# PROC106B_BT_DISPLAY.net
KiCad netlist of a schematic drawn in Altium Designer
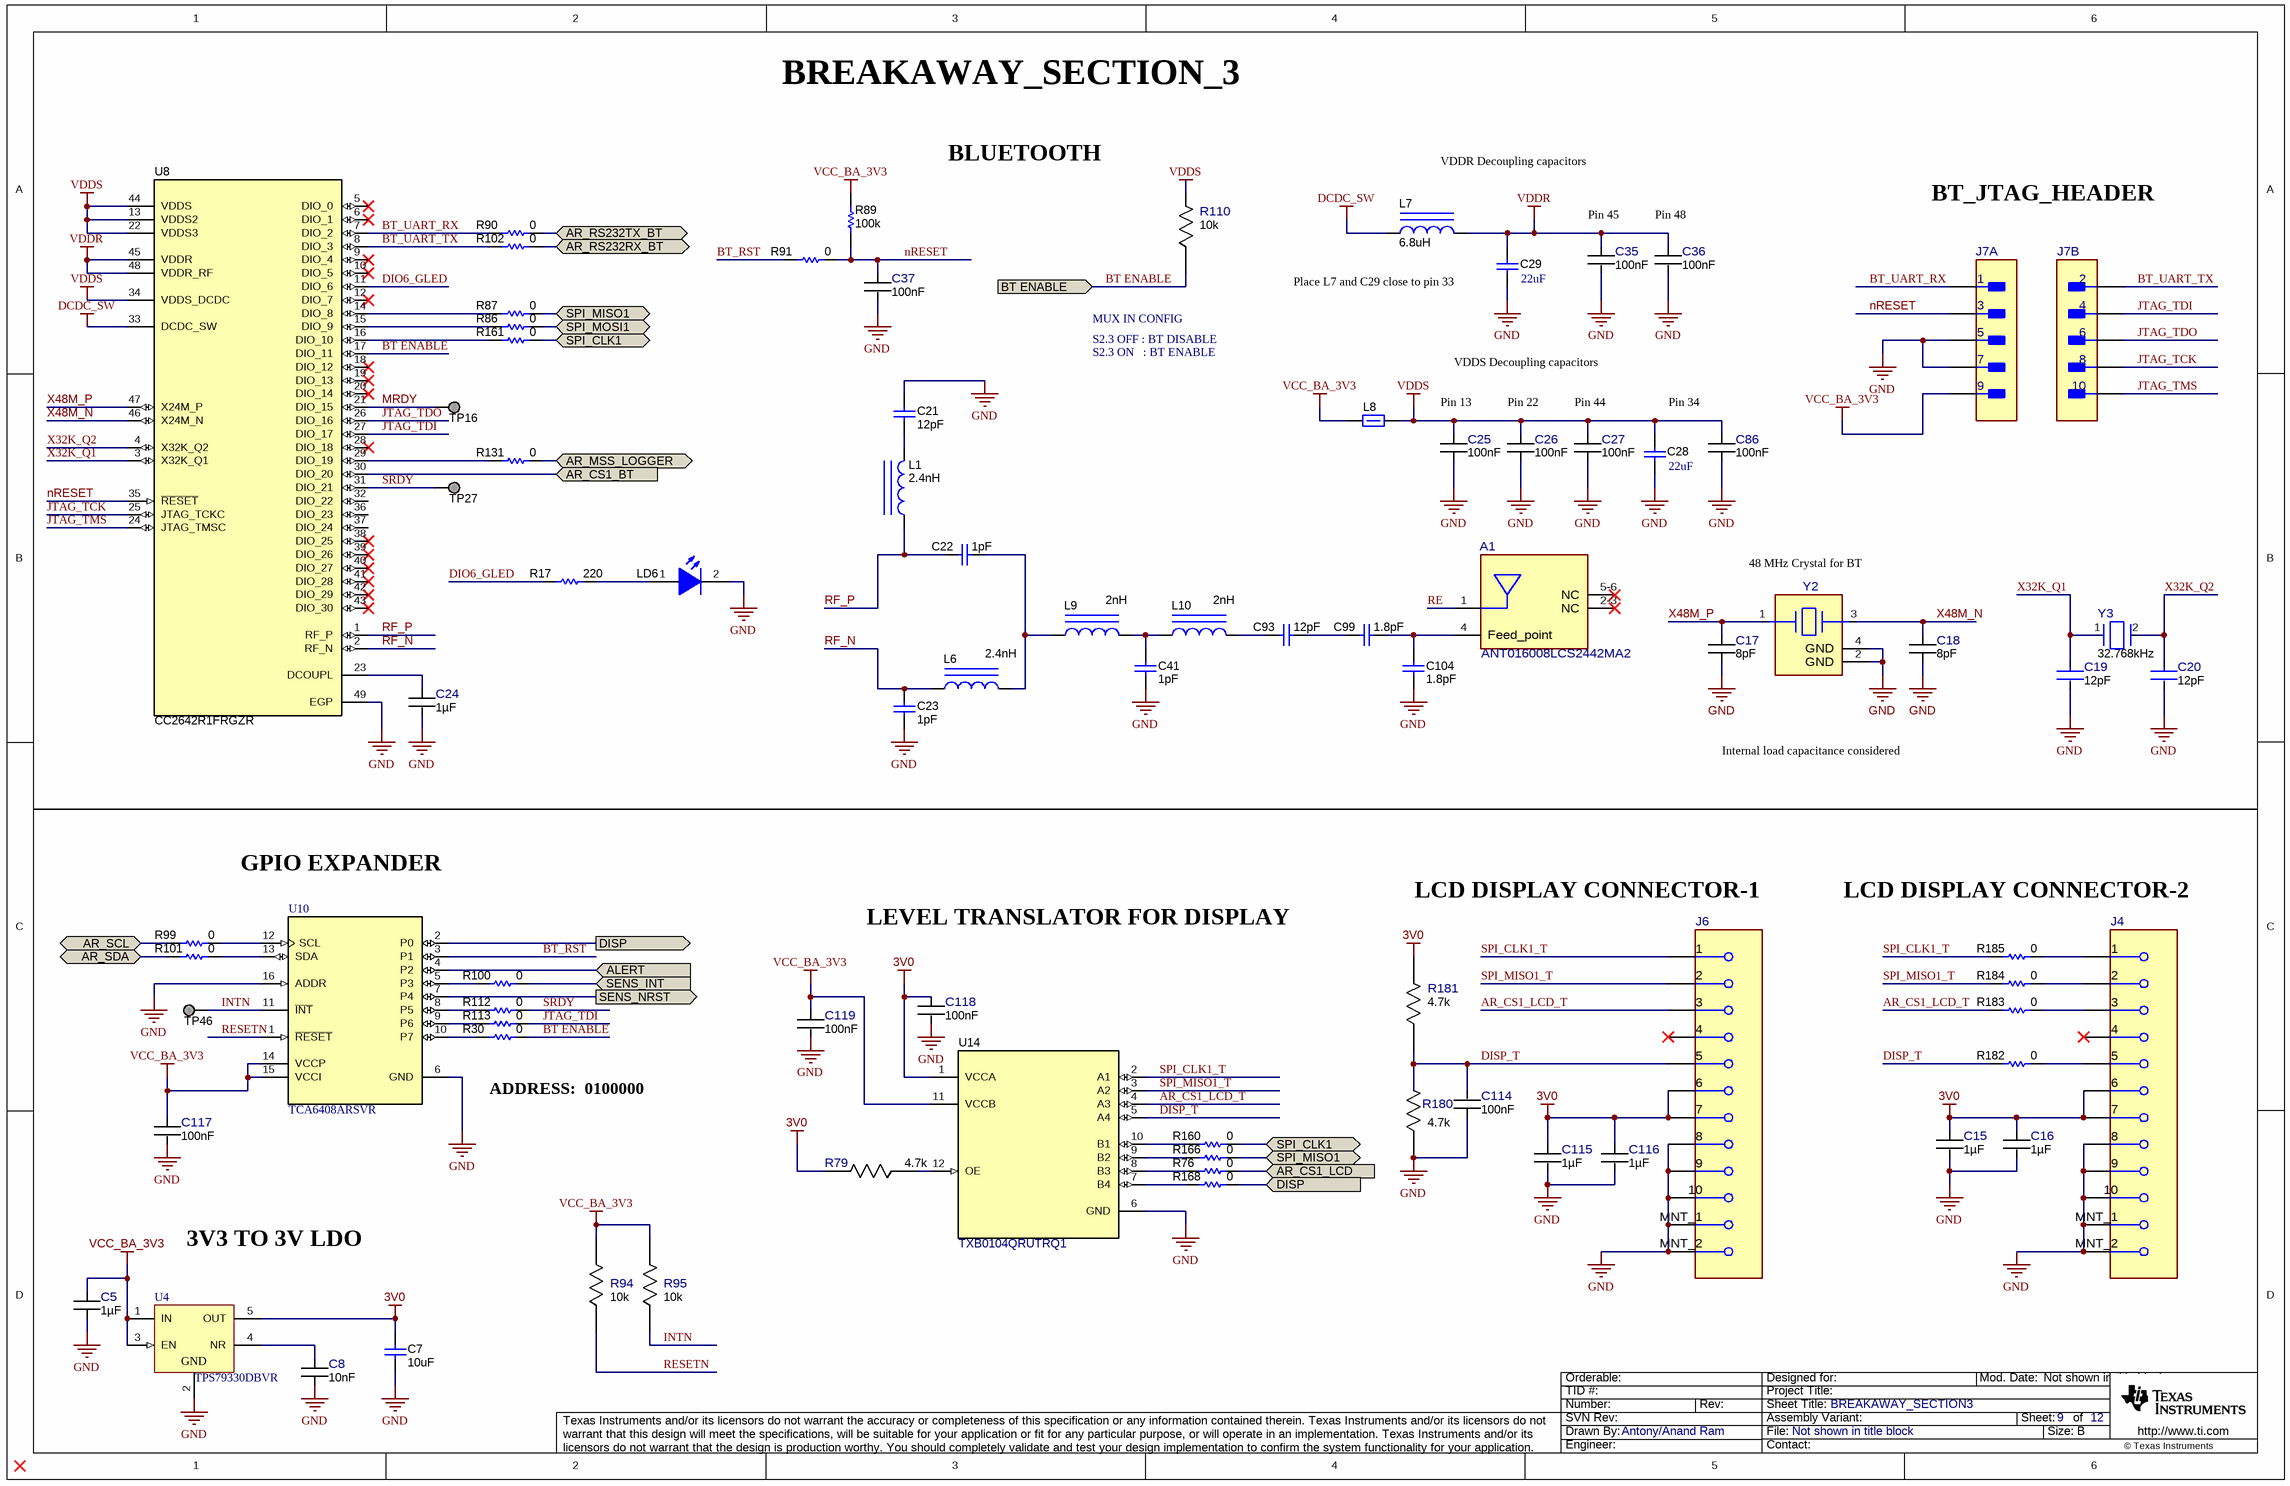
[diagram p0: PROC106B_BT_DISPLAY.SchDoc]

(export (version "E")
  (design (tool "Eeschema 10.0.6"))
  (components
    (comp (ref "A1")
      (value "ANT016008LCS2442MA2")
      (footprint "FP-ANT016008LCS2442MA2_SMT_ANT-0")
      (description "RF ANT 2.4GHZ CHIP SOLDER SMD")
      (fields (field (name "MANUFACTURER") "TDK Corporation"))
      (libsource (lib "Altium Vault - TI") (part "SYM-ANT016008LCS2442MA2"))
    )
    (comp (ref "C5")
      (value "CL03A105MO3NRNH")
      (footprint "FP-CL03A105MO3NRNH_0201-IPC_C")
      (description "1µF ±20% 16V Ceramic Capacitor X5R 0201")
      (fields (field (name "CAP_F") "1µF") (field (name "MANUFACTURER") "Samsung Electro-Mechanics"))
      (libsource (lib "Altium Vault - TI") (part "SYM-B32642B0223J"))
    )
    (comp (ref "C7")
      (value "10uF")
      (footprint "0402_070")
      (description "CAP, CERM, 10 uF, 10 V, +/- 20%, X5R, 0402")
      (fields
        (field (name "MANUFACTURER") "Samsung Electro-Mechanics")
        (field (name "PARTNUMBER") "CL05A106MP5NUNC")
      )
      (libsource (lib "Altium Vault - TI") (part "Capacitor"))
    )
    (comp (ref "C8")
      (value "CL03A103KA3NNNC")
      (footprint "FP-CL03A103KA3NNNC_0201-IPC_C")
      (description "CAP CER 10000PF 25V X5R 0201")
      (fields
        (field (name "CAP_F") "10nF")
        (field (name "MANUFACTURER") "Samsung Electro-Mechanics America, Inc")
      )
      (libsource (lib "Altium Vault - TI") (part "SYM-B32642B0223J"))
    )
    (comp (ref "C15")
      (value "CL03A105MO3NRNH")
      (footprint "FP-CL03A105MO3NRNH_0201-IPC_C")
      (description "1µF ±20% 16V Ceramic Capacitor X5R 0201")
      (fields (field (name "CAP_F") "1µF") (field (name "MANUFACTURER") "Samsung Electro-Mechanics"))
      (libsource (lib "Altium Vault - TI") (part "SYM-B32642B0223J"))
    )
    (comp (ref "C16")
      (value "CL03A105MO3NRNH")
      (footprint "FP-CL03A105MO3NRNH_0201-IPC_C")
      (description "1µF ±20% 16V Ceramic Capacitor X5R 0201")
      (fields (field (name "CAP_F") "1µF") (field (name "MANUFACTURER") "Samsung Electro-Mechanics"))
      (libsource (lib "Altium Vault - TI") (part "SYM-B32642B0223J"))
    )
    (comp (ref "C17")
      (value "GRM0335C1H8R0BA01D")
      (footprint "FP-GRM0335C1H8R0BA01D_0201 (0603 metric)-IPC_C")
      (description "Cap Ceramic 8pF 50V C0G 0.1pF SMD 0201 125°C Paper T/R")
      (fields (field (name "CAP_F") "8pF") (field (name "MANUFACTURER") "Murata"))
      (libsource (lib "Altium Vault - TI") (part "SYM-B32642B0223J"))
    )
    (comp (ref "C18")
      (value "GRM0335C1H8R0BA01D")
      (footprint "FP-GRM0335C1H8R0BA01D_0201 (0603 metric)-IPC_C")
      (description "Cap Ceramic 8pF 50V C0G 0.1pF SMD 0201 125°C Paper T/R")
      (fields (field (name "CAP_F") "8pF") (field (name "MANUFACTURER") "Murata"))
      (libsource (lib "Altium Vault - TI") (part "SYM-B32642B0223J"))
    )
    (comp (ref "C19")
      (value "250R05L120JV4T")
      (footprint "FP-250R05L120JV4T_0201-IPC_C")
      (description "CAP CER 12PF 25V C0G/NP0 0201")
      (fields (field (name "CAP_F") "12pF") (field (name "MANUFACTURER") "Johanson Technology Inc."))
      (libsource (lib "Altium Vault - TI") (part "SYM-CL31B335KAHVPNE"))
    )
    (comp (ref "C20")
      (value "250R05L120JV4T")
      (footprint "FP-250R05L120JV4T_0201-IPC_C")
      (description "CAP CER 12PF 25V C0G/NP0 0201")
      (fields (field (name "CAP_F") "12pF") (field (name "MANUFACTURER") "Johanson Technology Inc."))
      (libsource (lib "Altium Vault - TI") (part "SYM-CL31B335KAHVPNE"))
    )
    (comp (ref "C21")
      (value "CL05C120JB5NNNC")
      (footprint "0402L")
      (description "CAP, CERM, 12 pF, 50 V, +/- 5%, C0G/NP0, 0402")
      (fields
        (field (name "MANUFACTURER") "Samsung Electro-Mechanics")
        (field (name "VALUEDISPLAYED") "12pF")
        (field (name "PUBLISHER") "Texas Instruments")
      )
      (libsource (lib "Altium Vault - TI") (part "Capacitor"))
    )
    (comp (ref "C22")
      (value "GCM1555C1H1R0CA16D")
      (footprint "0402L")
      (description "CAP, CERM, 1 pF, 50 V,+/- 25%, C0G/NP0, AEC-Q200 Grade 1, 0402")
      (fields (field (name "VALUEDISPLAYED") "1pF") (field (name "MANUFACTURER") "MuRata"))
      (libsource (lib "Altium Vault - TI") (part "Capacitor"))
    )
    (comp (ref "C23")
      (value "GCM1555C1H1R0CA16D")
      (footprint "0402L")
      (description "CAP, CERM, 1 pF, 50 V,+/- 25%, C0G/NP0, AEC-Q200 Grade 1, 0402")
      (fields (field (name "VALUEDISPLAYED") "1pF") (field (name "MANUFACTURER") "MuRata"))
      (libsource (lib "Altium Vault - TI") (part "Capacitor"))
    )
    (comp (ref "C24")
      (value "CL03A105MO3NRNH")
      (footprint "FP-CL03A105MO3NRNH_0201-IPC_C")
      (description "1µF ±20% 16V Ceramic Capacitor X5R 0201")
      (fields (field (name "CAP_F") "1µF") (field (name "MANUFACTURER") "Samsung Electro-Mechanics"))
      (libsource (lib "Altium Vault - TI") (part "SYM-B32642B0223J"))
    )
    (comp (ref "C25")
      (value "GRM033R6YA104KE14D")
      (footprint "FP-GRM033R6YA104KE14D_0201 (0603 Metric)-IPC_C")
      (description "Cap Ceramic 0.1uF 35V X5R 10% Pad SMD 0201 85C T/R")
      (fields (field (name "CAP_F") "100nF") (field (name "MANUFACTURER") "Murata Electronics North America"))
      (libsource (lib "Altium Vault - TI") (part "SYM-B32642B0223J"))
    )
    (comp (ref "C26")
      (value "GRM033R6YA104KE14D")
      (footprint "FP-GRM033R6YA104KE14D_0201 (0603 Metric)-IPC_C")
      (description "Cap Ceramic 0.1uF 35V X5R 10% Pad SMD 0201 85C T/R")
      (fields (field (name "CAP_F") "100nF") (field (name "MANUFACTURER") "Murata Electronics North America"))
      (libsource (lib "Altium Vault - TI") (part "SYM-B32642B0223J"))
    )
    (comp (ref "C27")
      (value "GRM033R6YA104KE14D")
      (footprint "FP-GRM033R6YA104KE14D_0201 (0603 Metric)-IPC_C")
      (description "Cap Ceramic 0.1uF 35V X5R 10% Pad SMD 0201 85C T/R")
      (fields (field (name "CAP_F") "100nF") (field (name "MANUFACTURER") "Murata Electronics North America"))
      (libsource (lib "Altium Vault - TI") (part "SYM-B32642B0223J"))
    )
    (comp (ref "C28")
      (value "CL05A226MQ5N6J8")
      (footprint "0402S")
      (description "CAP CER 22UF 6.3V X5R 0402")
      (fields
        (field (name "MANUFACTURER") "Samsung Electro-Mechanics")
        (field (name "VALUEDISPLAYED") "22uF")
      )
      (libsource (lib "Altium Vault - TI") (part "Capacitor"))
    )
    (comp (ref "C29")
      (value "CL05A226MQ5N6J8")
      (footprint "0402S")
      (description "CAP CER 22UF 6.3V X5R 0402")
      (fields
        (field (name "MANUFACTURER") "Samsung Electro-Mechanics")
        (field (name "VALUEDISPLAYED") "22uF")
      )
      (libsource (lib "Altium Vault - TI") (part "Capacitor"))
    )
    (comp (ref "C35")
      (value "GRM033R6YA104KE14D")
      (footprint "FP-GRM033R6YA104KE14D_0201 (0603 Metric)-IPC_C")
      (description "Cap Ceramic 0.1uF 35V X5R 10% Pad SMD 0201 85C T/R")
      (fields (field (name "CAP_F") "100nF") (field (name "MANUFACTURER") "Murata Electronics North America"))
      (libsource (lib "Altium Vault - TI") (part "SYM-B32642B0223J"))
    )
    (comp (ref "C36")
      (value "GRM033R6YA104KE14D")
      (footprint "FP-GRM033R6YA104KE14D_0201 (0603 Metric)-IPC_C")
      (description "Cap Ceramic 0.1uF 35V X5R 10% Pad SMD 0201 85C T/R")
      (fields (field (name "CAP_F") "100nF") (field (name "MANUFACTURER") "Murata Electronics North America"))
      (libsource (lib "Altium Vault - TI") (part "SYM-B32642B0223J"))
    )
    (comp (ref "C37")
      (value "GRM033R6YA104KE14D")
      (footprint "FP-GRM033R6YA104KE14D_0201 (0603 Metric)-IPC_C")
      (description "Cap Ceramic 0.1uF 35V X5R 10% Pad SMD 0201 85C T/R")
      (fields (field (name "CAP_F") "100nF") (field (name "MANUFACTURER") "Murata Electronics North America"))
      (libsource (lib "Altium Vault - TI") (part "SYM-B32642B0223J"))
    )
    (comp (ref "C41")
      (value "GCM1555C1H1R0CA16D")
      (footprint "0402L")
      (description "CAP, CERM, 1 pF, 50 V,+/- 25%, C0G/NP0, AEC-Q200 Grade 1, 0402")
      (fields (field (name "VALUEDISPLAYED") "1pF") (field (name "MANUFACTURER") "MuRata"))
      (libsource (lib "Altium Vault - TI") (part "Capacitor"))
    )
    (comp (ref "C86")
      (value "GRM033R6YA104KE14D")
      (footprint "FP-GRM033R6YA104KE14D_0201 (0603 Metric)-IPC_C")
      (description "Cap Ceramic 0.1uF 35V X5R 10% Pad SMD 0201 85C T/R")
      (fields (field (name "CAP_F") "100nF") (field (name "MANUFACTURER") "Murata Electronics North America"))
      (libsource (lib "Altium Vault - TI") (part "SYM-B32642B0223J"))
    )
    (comp (ref "C93")
      (value "CL05C120JB5NNNC")
      (footprint "0402L")
      (description "CAP, CERM, 12 pF, 50 V, +/- 5%, C0G/NP0, 0402")
      (fields
        (field (name "MANUFACTURER") "Samsung Electro-Mechanics")
        (field (name "VALUEDISPLAYED") "12pF")
        (field (name "PUBLISHER") "Texas Instruments")
      )
      (libsource (lib "Altium Vault - TI") (part "Capacitor"))
    )
    (comp (ref "C99")
      (value "GJM1555C1H1R8BB01D")
      (footprint "0402L")
      (description "CAP, CERM, 1.8 pF, 50 V,+/- 6%, C0G/NP0, 0402")
      (fields (field (name "VALUEDISPLAYED") "1.8pF") (field (name "MANUFACTURER") "MuRata"))
      (libsource (lib "Altium Vault - TI") (part "Capacitor"))
    )
    (comp (ref "C104")
      (value "GJM1555C1H1R8BB01D")
      (footprint "0402L")
      (description "CAP, CERM, 1.8 pF, 50 V,+/- 6%, C0G/NP0, 0402")
      (fields (field (name "VALUEDISPLAYED") "1.8pF") (field (name "MANUFACTURER") "MuRata"))
      (libsource (lib "Altium Vault - TI") (part "Capacitor"))
    )
    (comp (ref "C114")
      (value "GRM033R6YA104KE14D")
      (footprint "FP-GRM033R6YA104KE14D_0201 (0603 Metric)-IPC_C")
      (description "Cap Ceramic 0.1uF 35V X5R 10% Pad SMD 0201 85C T/R")
      (fields (field (name "CAP_F") "100nF") (field (name "MANUFACTURER") "Murata Electronics North America"))
      (libsource (lib "Altium Vault - TI") (part "SYM-B32642B0223J"))
    )
    (comp (ref "C115")
      (value "CL03A105MO3NRNH")
      (footprint "FP-CL03A105MO3NRNH_0201-IPC_C")
      (description "1µF ±20% 16V Ceramic Capacitor X5R 0201")
      (fields (field (name "CAP_F") "1µF") (field (name "MANUFACTURER") "Samsung Electro-Mechanics"))
      (libsource (lib "Altium Vault - TI") (part "SYM-B32642B0223J"))
    )
    (comp (ref "C116")
      (value "CL03A105MO3NRNH")
      (footprint "FP-CL03A105MO3NRNH_0201-IPC_C")
      (description "1µF ±20% 16V Ceramic Capacitor X5R 0201")
      (fields (field (name "CAP_F") "1µF") (field (name "MANUFACTURER") "Samsung Electro-Mechanics"))
      (libsource (lib "Altium Vault - TI") (part "SYM-B32642B0223J"))
    )
    (comp (ref "C117")
      (value "GRM033R6YA104KE14D")
      (footprint "FP-GRM033R6YA104KE14D_0201 (0603 Metric)-IPC_C")
      (description "Cap Ceramic 0.1uF 35V X5R 10% Pad SMD 0201 85C T/R")
      (fields (field (name "CAP_F") "100nF") (field (name "MANUFACTURER") "Murata Electronics North America"))
      (libsource (lib "Altium Vault - TI") (part "SYM-B32642B0223J"))
    )
    (comp (ref "C118")
      (value "GRM033R6YA104KE14D")
      (footprint "FP-GRM033R6YA104KE14D_0201 (0603 Metric)-IPC_C")
      (description "Cap Ceramic 0.1uF 35V X5R 10% Pad SMD 0201 85C T/R")
      (fields (field (name "CAP_F") "100nF") (field (name "MANUFACTURER") "Murata Electronics North America"))
      (libsource (lib "Altium Vault - TI") (part "SYM-B32642B0223J"))
    )
    (comp (ref "C119")
      (value "GRM033R6YA104KE14D")
      (footprint "FP-GRM033R6YA104KE14D_0201 (0603 Metric)-IPC_C")
      (description "Cap Ceramic 0.1uF 35V X5R 10% Pad SMD 0201 85C T/R")
      (fields (field (name "CAP_F") "100nF") (field (name "MANUFACTURER") "Murata Electronics North America"))
      (libsource (lib "Altium Vault - TI") (part "SYM-B32642B0223J"))
    )
    (comp (ref "J4")
      (value "51441-1093")
      (footprint "FP-51441-1093_CONN_SMD_FFC-0")
      (fields (field (name "MANUFACTURER") "Molex"))
      (libsource (lib "Altium Vault - TI") (part "SYM-51441-1093"))
    )
    (comp (ref "J6")
      (value "51441-1093")
      (footprint "FP-51441-1093_CONN_SMD_FFC-0")
      (fields (field (name "MANUFACTURER") "Molex"))
      (libsource (lib "Altium Vault - TI") (part "SYM-51441-1093"))
    )
    (comp (ref "J7")
      (value "GRPB052MWCN-RC")
      (footprint "FP-GRPB052MWCN-RC_HDR10-MFG")
      (description "CONN HEADER R/A 10POS 1.27MM")
      (fields (field (name "MANUFACTURER") "Sullins"))
      (libsource (lib "Altium Vault - TI") (part "SYM-GRPB052MWCN-RC"))
    )
    (comp (ref "L1")
      (value "LQG15HS2N4S02D")
      (footprint "IND_LQG15H")
      (description "Inductor, Multilayer, Air Core, 2.4 nH, 0.3 A, 0.15 ohm, SMD")
      (fields
        (field (name "MANUFACTURER") "MuRata")
        (field (name "VALUEDISPLAYED") "2.4nH")
        (field (name "PUBLISHER") "Texas Instruments")
      )
      (libsource (lib "Altium Vault - TI") (part "Inductor_Iron"))
    )
    (comp (ref "L6")
      (value "LQG15HS2N4S02D")
      (footprint "IND_LQG15H")
      (description "Inductor, Multilayer, Air Core, 2.4 nH, 0.3 A, 0.15 ohm, SMD")
      (fields
        (field (name "MANUFACTURER") "MuRata")
        (field (name "VALUEDISPLAYED") "2.4nH")
        (field (name "PUBLISHER") "Texas Instruments")
      )
      (libsource (lib "Altium Vault - TI") (part "Inductor_Iron"))
    )
    (comp (ref "L7")
      (value "MLZ2012N6R8LT000")
      (footprint "0805_HV")
      (description "Inductor, Multilayer, Ferrite, 6.8 uH, 0.11 A, 0.25 ohm, SMD")
      (fields
        (field (name "MANUFACTURER") "TDK")
        (field (name "VALUEDISPLAYED") "6.8uH")
        (field (name "PUBLISHER") "Texas Instruments")
      )
      (libsource (lib "Altium Vault - TI") (part "Inductor_Iron"))
    )
    (comp (ref "L8")
      (value "BLM18HE152SN1D")
      (footprint "0603L")
      (description "Ferrite Bead, 1500 ohm @ 100 MHz, 0.5 A, 0603")
      (fields (field (name "MANUFACTURER") "MuRata") (field (name "PUBLISHER") "Texas Instruments"))
      (libsource (lib "Altium Vault - TI") (part "Ferrite_Bead"))
    )
    (comp (ref "L9")
      (value "LQG15HS2N0S02D")
      (footprint "IND_LQG15H")
      (description "Inductor, Multilayer, Air Core, 2 nH, 0.3 A, 0.1 ohm, SMD")
      (fields
        (field (name "MANUFACTURER") "MuRata")
        (field (name "VALUEDISPLAYED") "2nH")
        (field (name "PUBLISHER") "Texas Instruments")
      )
      (libsource (lib "Altium Vault - TI") (part "Inductor_Iron"))
    )
    (comp (ref "L10")
      (value "LQG15HS2N0S02D")
      (footprint "IND_LQG15H")
      (description "Inductor, Multilayer, Air Core, 2 nH, 0.3 A, 0.1 ohm, SMD")
      (fields
        (field (name "MANUFACTURER") "MuRata")
        (field (name "VALUEDISPLAYED") "2nH")
        (field (name "PUBLISHER") "Texas Instruments")
      )
      (libsource (lib "Altium Vault - TI") (part "Inductor_Iron"))
    )
    (comp (ref "LD6")
      (value "APHHS1005CGCK")
      (footprint "APHHS1005_Green")
      (description "LED, Green, SMD")
      (fields (field (name "MANUFACTURER") "Kingbright"))
      (libsource (lib "Altium Vault - TI") (part "LED"))
    )
    (comp (ref "R17")
      (value "220")
      (footprint "0201L")
      (description "RES, 220, 5%, 0.05 W, 0201")
      (fields
        (field (name "MANUFACTURER") "Yageo America")
        (field (name "PARTNUMBER") "RC0201JR-07220RL")
        (field (name "PUBLISHER") "Texas Instruments")
      )
      (libsource (lib "Altium Vault - TI") (part "Resistor"))
    )
    (comp (ref "R30")
      (value "RC0201JR-070RL")
      (footprint "FP-RC0201JR-070RL_0201 (0603 Metric)-MFG")
      (description "RES SMD 0 OHM JUMPER 1/20W 0201")
      (fields (field (name "MANUFACTURER") "Yageo") (field (name "RES_OHM") "0"))
      (libsource (lib "Altium Vault - TI") (part "SYM-WSR3R1500F"))
    )
    (comp (ref "R76")
      (value "RC0201JR-070RL")
      (footprint "FP-RC0201JR-070RL_0201 (0603 Metric)-IPC_C")
      (description "RES SMD 0 OHM JUMPER 1/20W 0201")
      (fields (field (name "MANUFACTURER") "Yageo") (field (name "RES_OHM") "0"))
      (libsource (lib "Altium Vault - TI") (part "SYM-WSR3R1500F"))
    )
    (comp (ref "R79")
      (value "ERJ-1GNF4701C")
      (footprint "FP-ERJ-1GNF4701C_0201-IPC_C")
      (description "RESISTOR, 0201, 0.05W, 1%, 4K7")
      (fields (field (name "MANUFACTURER") "Panasonic Electronic Components") (field (name "RES_OHM") "4.7k"))
      (libsource (lib "Altium Vault - TI") (part "SYM-PMR18EZPJ000"))
    )
    (comp (ref "R86")
      (value "RC0201JR-070RL")
      (footprint "FP-RC0201JR-070RL_0201 (0603 Metric)-IPC_C")
      (description "RES SMD 0 OHM JUMPER 1/20W 0201")
      (fields (field (name "MANUFACTURER") "Yageo") (field (name "RES_OHM") "0"))
      (libsource (lib "Altium Vault - TI") (part "SYM-WSR3R1500F"))
    )
    (comp (ref "R87")
      (value "RC0201JR-070RL")
      (footprint "FP-RC0201JR-070RL_0201 (0603 Metric)-IPC_C")
      (description "RES SMD 0 OHM JUMPER 1/20W 0201")
      (fields (field (name "MANUFACTURER") "Yageo") (field (name "RES_OHM") "0"))
      (libsource (lib "Altium Vault - TI") (part "SYM-WSR3R1500F"))
    )
    (comp (ref "R89")
      (value "100k")
      (footprint "0201L")
      (description "RES, 100 k, 1%, 0.05 W, 0201")
      (fields (field (name "MANUFACTURER") "Vishay-Dale") (field (name "PARTNUMBER") "CRCW0201100KFKED"))
      (libsource (lib "Altium Vault - TI") (part "Resistor"))
    )
    (comp (ref "R90")
      (value "RC0201JR-070RL")
      (footprint "FP-RC0201JR-070RL_0201 (0603 Metric)-IPC_C")
      (description "RES SMD 0 OHM JUMPER 1/20W 0201")
      (fields (field (name "MANUFACTURER") "Yageo") (field (name "RES_OHM") "0"))
      (libsource (lib "Altium Vault - TI") (part "SYM-WSR3R1500F"))
    )
    (comp (ref "R91")
      (value "RC0201JR-070RL")
      (footprint "FP-RC0201JR-070RL_0201 (0603 Metric)-IPC_C")
      (description "RES SMD 0 OHM JUMPER 1/20W 0201")
      (fields (field (name "MANUFACTURER") "Yageo") (field (name "RES_OHM") "0"))
      (libsource (lib "Altium Vault - TI") (part "SYM-WSR3R1500F"))
    )
    (comp (ref "R94")
      (value "RR0306P-103-D")
      (footprint "FP-RR0306P-103-D_0201-IPC_C")
      (description "10 kOhms ±0.5% 0.05W, 1/20W Chip Resistor 0201 (0603 Metric)  Thin Film")
      (fields (field (name "MANUFACTURER") "Susumu") (field (name "RES_OHM") "10k"))
      (libsource (lib "Altium Vault - TI") (part "SYM-PMR18EZPJ000"))
    )
    (comp (ref "R95")
      (value "RR0306P-103-D")
      (footprint "FP-RR0306P-103-D_0201-IPC_C")
      (description "10 kOhms ±0.5% 0.05W, 1/20W Chip Resistor 0201 (0603 Metric)  Thin Film")
      (fields (field (name "MANUFACTURER") "Susumu") (field (name "RES_OHM") "10k"))
      (libsource (lib "Altium Vault - TI") (part "SYM-PMR18EZPJ000"))
    )
    (comp (ref "R99")
      (value "RC0201JR-070RL")
      (footprint "FP-RC0201JR-070RL_0201 (0603 Metric)-IPC_C")
      (description "RES SMD 0 OHM JUMPER 1/20W 0201")
      (fields (field (name "MANUFACTURER") "Yageo") (field (name "RES_OHM") "0"))
      (libsource (lib "Altium Vault - TI") (part "SYM-WSR3R1500F"))
    )
    (comp (ref "R100")
      (value "RC0201JR-070RL")
      (footprint "FP-RC0201JR-070RL_0201 (0603 Metric)-IPC_C")
      (description "RES SMD 0 OHM JUMPER 1/20W 0201")
      (fields (field (name "MANUFACTURER") "Yageo") (field (name "RES_OHM") "0"))
      (libsource (lib "Altium Vault - TI") (part "SYM-WSR3R1500F"))
    )
    (comp (ref "R101")
      (value "RC0201JR-070RL")
      (footprint "FP-RC0201JR-070RL_0201 (0603 Metric)-IPC_C")
      (description "RES SMD 0 OHM JUMPER 1/20W 0201")
      (fields (field (name "MANUFACTURER") "Yageo") (field (name "RES_OHM") "0"))
      (libsource (lib "Altium Vault - TI") (part "SYM-WSR3R1500F"))
    )
    (comp (ref "R102")
      (value "RC0201JR-070RL")
      (footprint "FP-RC0201JR-070RL_0201 (0603 Metric)-IPC_C")
      (description "RES SMD 0 OHM JUMPER 1/20W 0201")
      (fields (field (name "MANUFACTURER") "Yageo") (field (name "RES_OHM") "0"))
      (libsource (lib "Altium Vault - TI") (part "SYM-WSR3R1500F"))
    )
    (comp (ref "R110")
      (value "RR0306P-103-D")
      (footprint "FP-RR0306P-103-D_0201-IPC_C")
      (description "10 kOhms ±0.5% 0.05W, 1/20W Chip Resistor 0201 (0603 Metric)  Thin Film")
      (fields (field (name "MANUFACTURER") "Susumu") (field (name "RES_OHM") "10k"))
      (libsource (lib "Altium Vault - TI") (part "SYM-PMR18EZPJ000"))
    )
    (comp (ref "R112")
      (value "RC0201JR-070RL")
      (footprint "FP-RC0201JR-070RL_0201 (0603 Metric)-IPC_C")
      (description "RES SMD 0 OHM JUMPER 1/20W 0201")
      (fields (field (name "MANUFACTURER") "Yageo") (field (name "RES_OHM") "0"))
      (libsource (lib "Altium Vault - TI") (part "SYM-WSR3R1500F"))
    )
    (comp (ref "R113")
      (value "RC0201JR-070RL")
      (footprint "FP-RC0201JR-070RL_0201 (0603 Metric)-IPC_C")
      (description "RES SMD 0 OHM JUMPER 1/20W 0201")
      (fields (field (name "MANUFACTURER") "Yageo") (field (name "RES_OHM") "0"))
      (libsource (lib "Altium Vault - TI") (part "SYM-WSR3R1500F"))
    )
    (comp (ref "R131")
      (value "RC0201JR-070RL")
      (footprint "FP-RC0201JR-070RL_0201 (0603 Metric)-IPC_C")
      (description "RES SMD 0 OHM JUMPER 1/20W 0201")
      (fields (field (name "MANUFACTURER") "Yageo") (field (name "RES_OHM") "0"))
      (libsource (lib "Altium Vault - TI") (part "SYM-WSR3R1500F"))
    )
    (comp (ref "R160")
      (value "RC0201JR-070RL")
      (footprint "FP-RC0201JR-070RL_0201 (0603 Metric)-IPC_C")
      (description "RES SMD 0 OHM JUMPER 1/20W 0201")
      (fields (field (name "MANUFACTURER") "Yageo") (field (name "RES_OHM") "0"))
      (libsource (lib "Altium Vault - TI") (part "SYM-WSR3R1500F"))
    )
    (comp (ref "R161")
      (value "RC0201JR-070RL")
      (footprint "FP-RC0201JR-070RL_0201 (0603 Metric)-IPC_C")
      (description "RES SMD 0 OHM JUMPER 1/20W 0201")
      (fields (field (name "MANUFACTURER") "Yageo") (field (name "RES_OHM") "0"))
      (libsource (lib "Altium Vault - TI") (part "SYM-WSR3R1500F"))
    )
    (comp (ref "R166")
      (value "RC0201JR-070RL")
      (footprint "FP-RC0201JR-070RL_0201 (0603 Metric)-IPC_C")
      (description "RES SMD 0 OHM JUMPER 1/20W 0201")
      (fields (field (name "MANUFACTURER") "Yageo") (field (name "RES_OHM") "0"))
      (libsource (lib "Altium Vault - TI") (part "SYM-WSR3R1500F"))
    )
    (comp (ref "R168")
      (value "RC0201JR-070RL")
      (footprint "FP-RC0201JR-070RL_0201 (0603 Metric)-IPC_C")
      (description "RES SMD 0 OHM JUMPER 1/20W 0201")
      (fields (field (name "MANUFACTURER") "Yageo") (field (name "RES_OHM") "0"))
      (libsource (lib "Altium Vault - TI") (part "SYM-WSR3R1500F"))
    )
    (comp (ref "R180")
      (value "ERJ-1GNF4701C")
      (footprint "FP-ERJ-1GNF4701C_0201-IPC_C")
      (description "RESISTOR, 0201, 0.05W, 1%, 4K7")
      (fields (field (name "MANUFACTURER") "Panasonic Electronic Components") (field (name "RES_OHM") "4.7k"))
      (libsource (lib "Altium Vault - TI") (part "SYM-PMR18EZPJ000"))
    )
    (comp (ref "R181")
      (value "ERJ-1GNF4701C")
      (footprint "FP-ERJ-1GNF4701C_0201-IPC_C")
      (description "RESISTOR, 0201, 0.05W, 1%, 4K7")
      (fields (field (name "MANUFACTURER") "Panasonic Electronic Components") (field (name "RES_OHM") "4.7k"))
      (libsource (lib "Altium Vault - TI") (part "SYM-PMR18EZPJ000"))
    )
    (comp (ref "R182")
      (value "RC0201JR-070RL")
      (footprint "FP-RC0201JR-070RL_0201 (0603 Metric)-IPC_C")
      (description "RES SMD 0 OHM JUMPER 1/20W 0201")
      (fields (field (name "MANUFACTURER") "Yageo") (field (name "RES_OHM") "0"))
      (libsource (lib "Altium Vault - TI") (part "SYM-WSR3R1500F"))
    )
    (comp (ref "R183")
      (value "RC0201JR-070RL")
      (footprint "FP-RC0201JR-070RL_0201 (0603 Metric)-IPC_C")
      (description "RES SMD 0 OHM JUMPER 1/20W 0201")
      (fields (field (name "MANUFACTURER") "Yageo") (field (name "RES_OHM") "0"))
      (libsource (lib "Altium Vault - TI") (part "SYM-WSR3R1500F"))
    )
    (comp (ref "R184")
      (value "RC0201JR-070RL")
      (footprint "FP-RC0201JR-070RL_0201 (0603 Metric)-IPC_C")
      (description "RES SMD 0 OHM JUMPER 1/20W 0201")
      (fields (field (name "MANUFACTURER") "Yageo") (field (name "RES_OHM") "0"))
      (libsource (lib "Altium Vault - TI") (part "SYM-WSR3R1500F"))
    )
    (comp (ref "R185")
      (value "RC0201JR-070RL")
      (footprint "FP-RC0201JR-070RL_0201 (0603 Metric)-IPC_C")
      (description "RES SMD 0 OHM JUMPER 1/20W 0201")
      (fields (field (name "MANUFACTURER") "Yageo") (field (name "RES_OHM") "0"))
      (libsource (lib "Altium Vault - TI") (part "SYM-WSR3R1500F"))
    )
    (comp (ref "TP16")
      (value "TESTPOINT")
      (footprint "TP_25MIL-SMT")
      (description "TEST POINT.  No entry in BOM.")
      (libsource (lib "Altium Vault - TI") (part "TESTPOINT"))
    )
    (comp (ref "TP27")
      (value "TESTPOINT")
      (footprint "TP_25MIL-SMT")
      (description "TEST POINT.  No entry in BOM.")
      (libsource (lib "Altium Vault - TI") (part "TESTPOINT"))
    )
    (comp (ref "TP46")
      (value "TESTPOINT")
      (footprint "TP_25MIL-SMT")
      (description "TEST POINT.  No entry in BOM.")
      (libsource (lib "Altium Vault - TI") (part "TESTPOINT"))
    )
    (comp (ref "U4")
      (value "TPS79330DBVR")
      (footprint "DBV0005A_N")
      (fields (field (name "MANUFACTURER") "Texas Instruments"))
      (libsource (lib "Altium Vault - TI") (part "TI-TPS79NXX-YYSOT5"))
    )
    (comp (ref "U8")
      (value "CC2642R1FRGZR")
      (footprint "RGZ0048A")
      (description "SimpleLink(TM) Bluetooth(R) 5 low energy Wireless MCU, RGZ0048A (VQFN-48)")
      (fields
        (field (name "PARTNUMBER") "CC2642R1FRGZR")
        (field (name "MANUFACTURER") "Texas Instruments")
        (field (name "ALTERNATE PARTNUMBER") "CC2642R1FRGZT")
      )
      (libsource (lib "Altium Vault - TI") (part "CC26xx_RGZ"))
    )
    (comp (ref "U10")
      (value "TCA6408ARSVR")
      (footprint "RSV0016A")
      (fields (field (name "MANUFACTURER") "Texas Instruments"))
      (libsource (lib "Altium Vault - TI") (part "TI-TCA6408A-UQFN_RSV-16"))
    )
    (comp (ref "U14")
      (value "TXB0104QRUTRQ1")
      (footprint "RUT0012A")
      (fields (field (name "MANUFACTURER") "Texas Instruments"))
      (libsource (lib "Altium Vault - TI") (part "TXB0104QRUTRQ1"))
    )
    (comp (ref "Y2")
      (value "CX2016DB48000C0WPLA2")
      (footprint "FP-CX2016DB48000C0WPLA2_SMD4-MFG")
      (description "48MHz ±20ppm Crystal 7pF 50 Ohms 4-SMD, No Lead")
      (fields (field (name "MANUFACTURER") "Kyocera"))
      (libsource (lib "Altium Vault - TI") (part "SYM-CX2016DB48000C0WPLA2"))
    )
    (comp (ref "Y3")
      (value "ABS05W-32.768KHZ-D-2-T")
      (footprint "FP-ABS05W-32.768KHZ-D-2-T_XTAL_SMT_1MM6_1MM0-MFG")
      (description "CRYSTAL 32.768KHZ 4PF SMD")
      (fields (field (name "FREQUENCY_FIXED") "32.768kHz") (field (name "MANUFACTURER") "Abracon LLC"))
      (libsource (lib "Altium Vault - TI") (part "SYM-ABS05W-32.768KHZ-D-2-T"))
    )
  )
  (nets
    (net (code "1") (name "/ALERT") (class "Default")
      (node (ref "U10") (pin "4") (pinfunction "P2_4") (pintype "bidirectional"))
    )
    (net (code "2") (name "/AR_CS1_BT") (class "Default")
      (node (ref "U8") (pin "30") (pinfunction "DIO_20_30") (pintype "bidirectional"))
    )
    (net (code "3") (name "/AR_CS1_LCD") (class "Default")
      (node (ref "R76") (pin "2") (pinfunction "2_2") (pintype "passive"))
    )
    (net (code "4") (name "/AR_CS1_LCD_T") (class "Default")
      (node (ref "J6") (pin "3") (pinfunction "3_3") (pintype "passive"))
      (node (ref "R183") (pin "1") (pinfunction "1_1") (pintype "passive"))
      (node (ref "U14") (pin "4") (pinfunction "A3_4") (pintype "bidirectional"))
    )
    (net (code "5") (name "/AR_MSS_LOGGER") (class "Default")
      (node (ref "R131") (pin "1") (pinfunction "1_1") (pintype "passive"))
    )
    (net (code "6") (name "/AR_RS232RX_BT") (class "Default")
      (node (ref "R102") (pin "1") (pinfunction "1_1") (pintype "passive"))
    )
    (net (code "7") (name "/AR_RS232TX_BT") (class "Default")
      (node (ref "R90") (pin "1") (pinfunction "1_1") (pintype "passive"))
    )
    (net (code "8") (name "/AR_SCL") (class "Default")
      (node (ref "R99") (pin "2") (pinfunction "2_2") (pintype "passive"))
    )
    (net (code "9") (name "/AR_SDA") (class "Default")
      (node (ref "R101") (pin "2") (pinfunction "2_2") (pintype "passive"))
    )
    (net (code "10") (name "/BT ENABLE") (class "Default")
      (node (ref "R110") (pin "1") (pinfunction "1_1") (pintype "passive"))
      (node (ref "R30") (pin "1") (pinfunction "1_1") (pintype "passive"))
      (node (ref "U8") (pin "17") (pinfunction "DIO_11_17") (pintype "bidirectional"))
    )
    (net (code "11") (name "/BT_RST") (class "Default")
      (node (ref "R91") (pin "2") (pinfunction "2_2") (pintype "passive"))
      (node (ref "U10") (pin "3") (pinfunction "P1_3") (pintype "bidirectional"))
    )
    (net (code "12") (name "/BT_UART_RX") (class "Default")
      (node (ref "J7") (pin "1") (pinfunction "1_1") (pintype "passive"))
      (node (ref "R90") (pin "2") (pinfunction "2_2") (pintype "passive"))
      (node (ref "U8") (pin "7") (pinfunction "DIO_2_7") (pintype "bidirectional"))
    )
    (net (code "13") (name "/BT_UART_TX") (class "Default")
      (node (ref "J7") (pin "2") (pinfunction "2_2") (pintype "passive"))
      (node (ref "R102") (pin "2") (pinfunction "2_2") (pintype "passive"))
      (node (ref "U8") (pin "8") (pinfunction "DIO_3_8") (pintype "bidirectional"))
    )
    (net (code "14") (name "/DIO6_GLED") (class "Default")
      (node (ref "R17") (pin "1") (pinfunction "1_1") (pintype "passive"))
      (node (ref "U8") (pin "11") (pinfunction "DIO_6_11") (pintype "bidirectional"))
    )
    (net (code "15") (name "/DISP") (class "Default")
      (node (ref "R168") (pin "2") (pinfunction "2_2") (pintype "passive"))
      (node (ref "U10") (pin "2") (pinfunction "P0_2") (pintype "bidirectional"))
    )
    (net (code "16") (name "/DISP_T") (class "Default")
      (node (ref "C114") (pin "2") (pinfunction "2_2") (pintype "passive"))
      (node (ref "J6") (pin "5") (pinfunction "5_5") (pintype "passive"))
      (node (ref "R180") (pin "2") (pinfunction "2_2") (pintype "passive"))
      (node (ref "R181") (pin "1") (pinfunction "1_1") (pintype "passive"))
      (node (ref "R182") (pin "1") (pinfunction "1_1") (pintype "passive"))
      (node (ref "U14") (pin "5") (pinfunction "A4_5") (pintype "bidirectional"))
    )
    (net (code "17") (name "/INTN") (class "Default")
      (node (ref "R95") (pin "1") (pinfunction "1_1") (pintype "passive"))
      (node (ref "TP46") (pin "1") (pintype "passive"))
      (node (ref "U10") (pin "11") (pinfunction "~{INT}_11") (pintype "open_collector"))
    )
    (net (code "18") (name "/JTAG_TCK") (class "Default")
      (node (ref "J7") (pin "8") (pinfunction "8_8") (pintype "passive"))
      (node (ref "U8") (pin "25") (pinfunction "JTAG_TCKC_25") (pintype "bidirectional"))
    )
    (net (code "19") (name "/JTAG_TDI") (class "Default")
      (node (ref "J7") (pin "4") (pinfunction "4_4") (pintype "passive"))
      (node (ref "R113") (pin "1") (pinfunction "1_1") (pintype "passive"))
      (node (ref "U8") (pin "27") (pinfunction "DIO_17_27") (pintype "bidirectional"))
    )
    (net (code "20") (name "/JTAG_TDO") (class "Default")
      (node (ref "J7") (pin "6") (pinfunction "6_6") (pintype "passive"))
      (node (ref "U8") (pin "26") (pinfunction "DIO_16_26") (pintype "bidirectional"))
    )
    (net (code "21") (name "/JTAG_TMS") (class "Default")
      (node (ref "J7") (pin "10") (pinfunction "10_10") (pintype "passive"))
      (node (ref "U8") (pin "24") (pinfunction "JTAG_TMSC_24") (pintype "bidirectional"))
    )
    (net (code "22") (name "/MRDY") (class "Default")
      (node (ref "TP16") (pin "1") (pintype "passive"))
      (node (ref "U8") (pin "21") (pinfunction "DIO_15_21") (pintype "bidirectional"))
    )
    (net (code "23") (name "/RE") (class "Default")
      (node (ref "A1") (pin "1") (pinfunction "Radiator_electrode_1") (pintype "passive"))
    )
    (net (code "24") (name "/RESETN") (class "Default")
      (node (ref "R94") (pin "1") (pinfunction "1_1") (pintype "passive"))
      (node (ref "U10") (pin "1") (pinfunction "~{RESET}_1") (pintype "input"))
    )
    (net (code "25") (name "/RF_N") (class "Default")
      (node (ref "C23") (pin "1") (pinfunction "1_1") (pintype "passive"))
      (node (ref "L6") (pin "1") (pinfunction "1_1") (pintype "passive"))
      (node (ref "U8") (pin "2") (pinfunction "RF_N_2") (pintype "bidirectional"))
    )
    (net (code "26") (name "/RF_P") (class "Default")
      (node (ref "C22") (pin "2") (pinfunction "2_2") (pintype "passive"))
      (node (ref "L1") (pin "1") (pinfunction "1_1") (pintype "passive"))
      (node (ref "U8") (pin "1") (pinfunction "RF_P_1") (pintype "bidirectional"))
    )
    (net (code "27") (name "/SENS_INT") (class "Default")
      (node (ref "R100") (pin "1") (pinfunction "1_1") (pintype "passive"))
    )
    (net (code "28") (name "/SENS_NRST") (class "Default")
      (node (ref "U10") (pin "7") (pinfunction "P4_7") (pintype "bidirectional"))
    )
    (net (code "29") (name "/SPI_CLK1") (class "Default")
      (node (ref "R160") (pin "2") (pinfunction "2_2") (pintype "passive"))
      (node (ref "R161") (pin "1") (pinfunction "1_1") (pintype "passive"))
    )
    (net (code "30") (name "/SPI_CLK1_T") (class "Default")
      (node (ref "J6") (pin "1") (pinfunction "1_1") (pintype "passive"))
      (node (ref "R185") (pin "1") (pinfunction "1_1") (pintype "passive"))
      (node (ref "U14") (pin "2") (pinfunction "A1_2") (pintype "bidirectional"))
    )
    (net (code "31") (name "/SPI_MISO1") (class "Default")
      (node (ref "R166") (pin "2") (pinfunction "2_2") (pintype "passive"))
      (node (ref "R87") (pin "1") (pinfunction "1_1") (pintype "passive"))
    )
    (net (code "32") (name "/SPI_MISO1_T") (class "Default")
      (node (ref "J6") (pin "2") (pinfunction "2_2") (pintype "passive"))
      (node (ref "R184") (pin "1") (pinfunction "1_1") (pintype "passive"))
      (node (ref "U14") (pin "3") (pinfunction "A2_3") (pintype "bidirectional"))
    )
    (net (code "33") (name "/SPI_MOSI1") (class "Default")
      (node (ref "R86") (pin "1") (pinfunction "1_1") (pintype "passive"))
    )
    (net (code "34") (name "/SRDY") (class "Default")
      (node (ref "R112") (pin "1") (pinfunction "1_1") (pintype "passive"))
      (node (ref "TP27") (pin "1") (pintype "passive"))
      (node (ref "U8") (pin "31") (pinfunction "DIO_21_31") (pintype "bidirectional"))
    )
    (net (code "35") (name "/X32K_Q1") (class "Default")
      (node (ref "C19") (pin "1") (pinfunction "1_1") (pintype "passive"))
      (node (ref "U8") (pin "3") (pinfunction "X32K_Q1_3") (pintype "bidirectional"))
      (node (ref "Y3") (pin "1") (pinfunction "1_1") (pintype "passive"))
    )
    (net (code "36") (name "/X32K_Q2") (class "Default")
      (node (ref "C20") (pin "1") (pinfunction "1_1") (pintype "passive"))
      (node (ref "U8") (pin "4") (pinfunction "X32K_Q2_4") (pintype "bidirectional"))
      (node (ref "Y3") (pin "2") (pinfunction "2_2") (pintype "passive"))
    )
    (net (code "37") (name "/X48M_N") (class "Default")
      (node (ref "C18") (pin "1") (pinfunction "1_1") (pintype "passive"))
      (node (ref "U8") (pin "46") (pinfunction "X24M_N_46") (pintype "bidirectional"))
      (node (ref "Y2") (pin "3") (pinfunction "2_HOT_3") (pintype "passive"))
    )
    (net (code "38") (name "/X48M_P") (class "Default")
      (node (ref "C17") (pin "1") (pinfunction "1_1") (pintype "passive"))
      (node (ref "U8") (pin "47") (pinfunction "X24M_P_47") (pintype "bidirectional"))
      (node (ref "Y2") (pin "1") (pinfunction "1_HOT_1") (pintype "passive"))
    )
    (net (code "39") (name "/nRESET") (class "Default")
      (node (ref "C37") (pin "1") (pinfunction "1_1") (pintype "passive"))
      (node (ref "J7") (pin "3") (pinfunction "3_3") (pintype "passive"))
      (node (ref "R89") (pin "1") (pinfunction "1_1") (pintype "passive"))
      (node (ref "R91") (pin "1") (pinfunction "1_1") (pintype "passive"))
      (node (ref "U8") (pin "35") (pinfunction "RESET_35") (pintype "input"))
    )
    (net (code "40") (name "3V0") (class "Default")
      (node (ref "C115") (pin "1") (pinfunction "1_1") (pintype "passive"))
      (node (ref "C116") (pin "1") (pinfunction "1_1") (pintype "passive"))
      (node (ref "C118") (pin "1") (pinfunction "1_1") (pintype "passive"))
      (node (ref "C15") (pin "1") (pinfunction "1_1") (pintype "passive"))
      (node (ref "C16") (pin "1") (pinfunction "1_1") (pintype "passive"))
      (node (ref "C7") (pin "1") (pinfunction "1_1") (pintype "passive"))
      (node (ref "J4") (pin "6") (pinfunction "6_6") (pintype "passive"))
      (node (ref "J4") (pin "7") (pinfunction "7_7") (pintype "passive"))
      (node (ref "J6") (pin "6") (pinfunction "6_6") (pintype "passive"))
      (node (ref "J6") (pin "7") (pinfunction "7_7") (pintype "passive"))
      (node (ref "R181") (pin "2") (pinfunction "2_2") (pintype "passive"))
      (node (ref "R79") (pin "2") (pinfunction "2_2") (pintype "passive"))
      (node (ref "U14") (pin "1") (pinfunction "VCCA_1") (pintype "power_in"))
      (node (ref "U4") (pin "5") (pinfunction "OUT_5") (pintype "power_in"))
    )
    (net (code "41") (name "DCDC_SW") (class "Default")
      (node (ref "L7") (pin "1") (pinfunction "1_1") (pintype "passive"))
      (node (ref "U8") (pin "33") (pinfunction "DCDC_SW_33") (pintype "power_in"))
    )
    (net (code "42") (name "GND") (class "Default")
      (node (ref "C104") (pin "2") (pinfunction "2_2") (pintype "passive"))
      (node (ref "C114") (pin "1") (pinfunction "1_1") (pintype "passive"))
      (node (ref "C115") (pin "2") (pinfunction "2_2") (pintype "passive"))
      (node (ref "C116") (pin "2") (pinfunction "2_2") (pintype "passive"))
      (node (ref "C117") (pin "2") (pinfunction "2_2") (pintype "passive"))
      (node (ref "C118") (pin "2") (pinfunction "2_2") (pintype "passive"))
      (node (ref "C119") (pin "2") (pinfunction "2_2") (pintype "passive"))
      (node (ref "C15") (pin "2") (pinfunction "2_2") (pintype "passive"))
      (node (ref "C16") (pin "2") (pinfunction "2_2") (pintype "passive"))
      (node (ref "C17") (pin "2") (pinfunction "2_2") (pintype "passive"))
      (node (ref "C18") (pin "2") (pinfunction "2_2") (pintype "passive"))
      (node (ref "C19") (pin "2") (pinfunction "2_2") (pintype "passive"))
      (node (ref "C20") (pin "2") (pinfunction "2_2") (pintype "passive"))
      (node (ref "C21") (pin "1") (pinfunction "1_1") (pintype "passive"))
      (node (ref "C23") (pin "2") (pinfunction "2_2") (pintype "passive"))
      (node (ref "C24") (pin "2") (pinfunction "2_2") (pintype "passive"))
      (node (ref "C25") (pin "2") (pinfunction "2_2") (pintype "passive"))
      (node (ref "C26") (pin "2") (pinfunction "2_2") (pintype "passive"))
      (node (ref "C27") (pin "2") (pinfunction "2_2") (pintype "passive"))
      (node (ref "C28") (pin "2") (pinfunction "2_2") (pintype "passive"))
      (node (ref "C29") (pin "2") (pinfunction "2_2") (pintype "passive"))
      (node (ref "C35") (pin "2") (pinfunction "2_2") (pintype "passive"))
      (node (ref "C36") (pin "2") (pinfunction "2_2") (pintype "passive"))
      (node (ref "C37") (pin "2") (pinfunction "2_2") (pintype "passive"))
      (node (ref "C41") (pin "2") (pinfunction "2_2") (pintype "passive"))
      (node (ref "C5") (pin "2") (pinfunction "2_2") (pintype "passive"))
      (node (ref "C7") (pin "2") (pinfunction "2_2") (pintype "passive"))
      (node (ref "C8") (pin "2") (pinfunction "2_2") (pintype "passive"))
      (node (ref "C86") (pin "2") (pinfunction "2_2") (pintype "passive"))
      (node (ref "J4") (pin "10") (pinfunction "10_10") (pintype "passive"))
      (node (ref "J4") (pin "11") (pinfunction "MNT_1_11") (pintype "passive"))
      (node (ref "J4") (pin "12") (pinfunction "MNT_2_12") (pintype "passive"))
      (node (ref "J4") (pin "8") (pinfunction "8_8") (pintype "passive"))
      (node (ref "J4") (pin "9") (pinfunction "9_9") (pintype "passive"))
      (node (ref "J6") (pin "10") (pinfunction "10_10") (pintype "passive"))
      (node (ref "J6") (pin "11") (pinfunction "MNT_1_11") (pintype "passive"))
      (node (ref "J6") (pin "12") (pinfunction "MNT_2_12") (pintype "passive"))
      (node (ref "J6") (pin "8") (pinfunction "8_8") (pintype "passive"))
      (node (ref "J6") (pin "9") (pinfunction "9_9") (pintype "passive"))
      (node (ref "J7") (pin "5") (pinfunction "5_5") (pintype "passive"))
      (node (ref "J7") (pin "7") (pinfunction "7_7") (pintype "passive"))
      (node (ref "LD6") (pin "2") (pinfunction "K_2") (pintype "passive"))
      (node (ref "R180") (pin "1") (pinfunction "1_1") (pintype "passive"))
      (node (ref "U10") (pin "16") (pinfunction "ADDR_16") (pintype "input"))
      (node (ref "U10") (pin "6") (pinfunction "GND_6") (pintype "power_in"))
      (node (ref "U14") (pin "6") (pinfunction "GND_6") (pintype "power_in"))
      (node (ref "U4") (pin "2") (pinfunction "GND_2") (pintype "power_in"))
      (node (ref "U8") (pin "49") (pinfunction "EGP_49") (pintype "power_in"))
      (node (ref "Y2") (pin "2") (pinfunction "GND_2") (pintype "power_in"))
      (node (ref "Y2") (pin "4") (pinfunction "GND_4") (pintype "power_in"))
    )
    (net (code "43") (name "Net-(A1-Feed_point)") (class "Default")
      (node (ref "A1") (pin "4") (pinfunction "Feed_point_4") (pintype "passive"))
      (node (ref "C104") (pin "1") (pinfunction "1_1") (pintype "passive"))
      (node (ref "C99") (pin "1") (pinfunction "1_1") (pintype "passive"))
    )
    (net (code "44") (name "Net-(C21-Pad2)") (class "Default")
      (node (ref "C21") (pin "2") (pinfunction "2_2") (pintype "passive"))
      (node (ref "L1") (pin "2") (pinfunction "2_2") (pintype "passive"))
    )
    (net (code "45") (name "Net-(C22-Pad1)") (class "Default")
      (node (ref "C22") (pin "1") (pinfunction "1_1") (pintype "passive"))
      (node (ref "L6") (pin "2") (pinfunction "2_2") (pintype "passive"))
      (node (ref "L9") (pin "1") (pinfunction "1_1") (pintype "passive"))
    )
    (net (code "46") (name "Net-(C41-Pad1)") (class "Default")
      (node (ref "C41") (pin "1") (pinfunction "1_1") (pintype "passive"))
      (node (ref "L10") (pin "1") (pinfunction "1_1") (pintype "passive"))
      (node (ref "L9") (pin "2") (pinfunction "2_2") (pintype "passive"))
    )
    (net (code "47") (name "Net-(C93-Pad1)") (class "Default")
      (node (ref "C93") (pin "1") (pinfunction "1_1") (pintype "passive"))
      (node (ref "C99") (pin "2") (pinfunction "2_2") (pintype "passive"))
    )
    (net (code "48") (name "Net-(C93-Pad2)") (class "Default")
      (node (ref "C93") (pin "2") (pinfunction "2_2") (pintype "passive"))
      (node (ref "L10") (pin "2") (pinfunction "2_2") (pintype "passive"))
    )
    (net (code "49") (name "Net-(J4-Pad1)") (class "Default")
      (node (ref "J4") (pin "1") (pinfunction "1_1") (pintype "passive"))
      (node (ref "R185") (pin "2") (pinfunction "2_2") (pintype "passive"))
    )
    (net (code "50") (name "Net-(J4-Pad2)") (class "Default")
      (node (ref "J4") (pin "2") (pinfunction "2_2") (pintype "passive"))
      (node (ref "R184") (pin "2") (pinfunction "2_2") (pintype "passive"))
    )
    (net (code "51") (name "Net-(J4-Pad3)") (class "Default")
      (node (ref "J4") (pin "3") (pinfunction "3_3") (pintype "passive"))
      (node (ref "R183") (pin "2") (pinfunction "2_2") (pintype "passive"))
    )
    (net (code "52") (name "Net-(J4-Pad5)") (class "Default")
      (node (ref "J4") (pin "5") (pinfunction "5_5") (pintype "passive"))
      (node (ref "R182") (pin "2") (pinfunction "2_2") (pintype "passive"))
    )
    (net (code "53") (name "Net-(LD6-A)") (class "Default")
      (node (ref "LD6") (pin "1") (pinfunction "A_1") (pintype "passive"))
      (node (ref "R17") (pin "2") (pinfunction "2_2") (pintype "passive"))
    )
    (net (code "54") (name "Net-(U4-NR)") (class "Default")
      (node (ref "C8") (pin "1") (pinfunction "1_1") (pintype "passive"))
      (node (ref "U4") (pin "4") (pinfunction "NR_4") (pintype "passive"))
    )
    (net (code "55") (name "Net-(U8-DCOUPL)") (class "Default")
      (node (ref "C24") (pin "1") (pinfunction "1_1") (pintype "passive"))
      (node (ref "U8") (pin "23") (pinfunction "DCOUPL_23") (pintype "power_in"))
    )
    (net (code "56") (name "Net-(U8-DIO_8)") (class "Default")
      (node (ref "R87") (pin "2") (pinfunction "2_2") (pintype "passive"))
      (node (ref "U8") (pin "14") (pinfunction "DIO_8_14") (pintype "bidirectional"))
    )
    (net (code "57") (name "Net-(U8-DIO_9)") (class "Default")
      (node (ref "R86") (pin "2") (pinfunction "2_2") (pintype "passive"))
      (node (ref "U8") (pin "15") (pinfunction "DIO_9_15") (pintype "bidirectional"))
    )
    (net (code "58") (name "Net-(U8-DIO_10)") (class "Default")
      (node (ref "R161") (pin "2") (pinfunction "2_2") (pintype "passive"))
      (node (ref "U8") (pin "16") (pinfunction "DIO_10_16") (pintype "bidirectional"))
    )
    (net (code "59") (name "Net-(U8-DIO_19)") (class "Default")
      (node (ref "R131") (pin "2") (pinfunction "2_2") (pintype "passive"))
      (node (ref "U8") (pin "29") (pinfunction "DIO_19_29") (pintype "bidirectional"))
    )
    (net (code "60") (name "Net-(U10-P3)") (class "Default")
      (node (ref "R100") (pin "2") (pinfunction "2_2") (pintype "passive"))
      (node (ref "U10") (pin "5") (pinfunction "P3_5") (pintype "bidirectional"))
    )
    (net (code "61") (name "Net-(U10-P5)") (class "Default")
      (node (ref "R112") (pin "2") (pinfunction "2_2") (pintype "passive"))
      (node (ref "U10") (pin "8") (pinfunction "P5_8") (pintype "bidirectional"))
    )
    (net (code "62") (name "Net-(U10-P6)") (class "Default")
      (node (ref "R113") (pin "2") (pinfunction "2_2") (pintype "passive"))
      (node (ref "U10") (pin "9") (pinfunction "P6_9") (pintype "bidirectional"))
    )
    (net (code "63") (name "Net-(U10-P7)") (class "Default")
      (node (ref "R30") (pin "2") (pinfunction "2_2") (pintype "passive"))
      (node (ref "U10") (pin "10") (pinfunction "P7_10") (pintype "bidirectional"))
    )
    (net (code "64") (name "Net-(U10-SCL)") (class "Default")
      (node (ref "R99") (pin "1") (pinfunction "1_1") (pintype "passive"))
      (node (ref "U10") (pin "12") (pinfunction "SCL_12") (pintype "input"))
    )
    (net (code "65") (name "Net-(U10-SDA)") (class "Default")
      (node (ref "R101") (pin "1") (pinfunction "1_1") (pintype "passive"))
      (node (ref "U10") (pin "13") (pinfunction "SDA_13") (pintype "bidirectional"))
    )
    (net (code "66") (name "Net-(U14-B1)") (class "Default")
      (node (ref "R160") (pin "1") (pinfunction "1_1") (pintype "passive"))
      (node (ref "U14") (pin "10") (pinfunction "B1_10") (pintype "bidirectional"))
    )
    (net (code "67") (name "Net-(U14-B2)") (class "Default")
      (node (ref "R166") (pin "1") (pinfunction "1_1") (pintype "passive"))
      (node (ref "U14") (pin "9") (pinfunction "B2_9") (pintype "bidirectional"))
    )
    (net (code "68") (name "Net-(U14-B3)") (class "Default")
      (node (ref "R76") (pin "1") (pinfunction "1_1") (pintype "passive"))
      (node (ref "U14") (pin "8") (pinfunction "B3_8") (pintype "bidirectional"))
    )
    (net (code "69") (name "Net-(U14-B4)") (class "Default")
      (node (ref "R168") (pin "1") (pinfunction "1_1") (pintype "passive"))
      (node (ref "U14") (pin "7") (pinfunction "B4_7") (pintype "bidirectional"))
    )
    (net (code "70") (name "Net-(U14-OE)") (class "Default")
      (node (ref "R79") (pin "1") (pinfunction "1_1") (pintype "passive"))
      (node (ref "U14") (pin "12") (pinfunction "OE_12") (pintype "input"))
    )
    (net (code "71") (name "VCC_BA_3V3") (class "Default")
      (node (ref "C117") (pin "1") (pinfunction "1_1") (pintype "passive"))
      (node (ref "C119") (pin "1") (pinfunction "1_1") (pintype "passive"))
      (node (ref "C5") (pin "1") (pinfunction "1_1") (pintype "passive"))
      (node (ref "J7") (pin "9") (pinfunction "9_9") (pintype "passive"))
      (node (ref "L8") (pin "1") (pinfunction "1_1") (pintype "passive"))
      (node (ref "R89") (pin "2") (pinfunction "2_2") (pintype "passive"))
      (node (ref "R94") (pin "2") (pinfunction "2_2") (pintype "passive"))
      (node (ref "R95") (pin "2") (pinfunction "2_2") (pintype "passive"))
      (node (ref "U10") (pin "14") (pinfunction "VCCP_14") (pintype "power_in"))
      (node (ref "U10") (pin "15") (pinfunction "VCCI_15") (pintype "power_in"))
      (node (ref "U14") (pin "11") (pinfunction "VCCB_11") (pintype "power_in"))
      (node (ref "U4") (pin "1") (pinfunction "IN_1") (pintype "power_in"))
      (node (ref "U4") (pin "3") (pinfunction "EN_3") (pintype "input"))
    )
    (net (code "72") (name "VDDR") (class "Default")
      (node (ref "C29") (pin "1") (pinfunction "1_1") (pintype "passive"))
      (node (ref "C35") (pin "1") (pinfunction "1_1") (pintype "passive"))
      (node (ref "C36") (pin "1") (pinfunction "1_1") (pintype "passive"))
      (node (ref "L7") (pin "2") (pinfunction "2_2") (pintype "passive"))
      (node (ref "U8") (pin "45") (pinfunction "VDDR_45") (pintype "power_in"))
      (node (ref "U8") (pin "48") (pinfunction "VDDR_RF_48") (pintype "power_in"))
    )
    (net (code "73") (name "VDDS") (class "Default")
      (node (ref "C25") (pin "1") (pinfunction "1_1") (pintype "passive"))
      (node (ref "C26") (pin "1") (pinfunction "1_1") (pintype "passive"))
      (node (ref "C27") (pin "1") (pinfunction "1_1") (pintype "passive"))
      (node (ref "C28") (pin "1") (pinfunction "1_1") (pintype "passive"))
      (node (ref "C86") (pin "1") (pinfunction "1_1") (pintype "passive"))
      (node (ref "L8") (pin "2") (pinfunction "2_2") (pintype "passive"))
      (node (ref "R110") (pin "2") (pinfunction "2_2") (pintype "passive"))
      (node (ref "U8") (pin "13") (pinfunction "VDDS2_13") (pintype "power_in"))
      (node (ref "U8") (pin "22") (pinfunction "VDDS3_22") (pintype "power_in"))
      (node (ref "U8") (pin "34") (pinfunction "VDDS_DCDC_34") (pintype "power_in"))
      (node (ref "U8") (pin "44") (pinfunction "VDDS_44") (pintype "power_in"))
    )
    (net (code "74") (name "unconnected-(A1-NC-Pad2-3)") (class "Default")
      (node (ref "A1") (pin "2-3") (pinfunction "NC_2-3") (pintype "passive+no_connect"))
    )
    (net (code "75") (name "unconnected-(A1-NC-Pad5-6)") (class "Default")
      (node (ref "A1") (pin "5-6") (pinfunction "NC_5-6") (pintype "passive+no_connect"))
    )
    (net (code "76") (name "unconnected-(J4-Pad4)") (class "Default")
      (node (ref "J4") (pin "4") (pinfunction "4_4") (pintype "passive+no_connect"))
    )
    (net (code "77") (name "unconnected-(J6-Pad4)") (class "Default")
      (node (ref "J6") (pin "4") (pinfunction "4_4") (pintype "passive+no_connect"))
    )
    (net (code "78") (name "unconnected-(U8-DIO_0-Pad5)") (class "Default")
      (node (ref "U8") (pin "5") (pinfunction "DIO_0_5") (pintype "bidirectional+no_connect"))
    )
    (net (code "79") (name "unconnected-(U8-DIO_1-Pad6)") (class "Default")
      (node (ref "U8") (pin "6") (pinfunction "DIO_1_6") (pintype "bidirectional+no_connect"))
    )
    (net (code "80") (name "unconnected-(U8-DIO_4-Pad9)") (class "Default")
      (node (ref "U8") (pin "9") (pinfunction "DIO_4_9") (pintype "bidirectional+no_connect"))
    )
    (net (code "81") (name "unconnected-(U8-DIO_5-Pad10)") (class "Default")
      (node (ref "U8") (pin "10") (pinfunction "DIO_5_10") (pintype "bidirectional+no_connect"))
    )
    (net (code "82") (name "unconnected-(U8-DIO_7-Pad12)") (class "Default")
      (node (ref "U8") (pin "12") (pinfunction "DIO_7_12") (pintype "bidirectional+no_connect"))
    )
    (net (code "83") (name "unconnected-(U8-DIO_12-Pad18)") (class "Default")
      (node (ref "U8") (pin "18") (pinfunction "DIO_12_18") (pintype "bidirectional+no_connect"))
    )
    (net (code "84") (name "unconnected-(U8-DIO_13-Pad19)") (class "Default")
      (node (ref "U8") (pin "19") (pinfunction "DIO_13_19") (pintype "bidirectional+no_connect"))
    )
    (net (code "85") (name "unconnected-(U8-DIO_14-Pad20)") (class "Default")
      (node (ref "U8") (pin "20") (pinfunction "DIO_14_20") (pintype "bidirectional+no_connect"))
    )
    (net (code "86") (name "unconnected-(U8-DIO_18-Pad28)") (class "Default")
      (node (ref "U8") (pin "28") (pinfunction "DIO_18_28") (pintype "bidirectional+no_connect"))
    )
    (net (code "87") (name "unconnected-(U8-DIO_22-Pad32)") (class "Default")
      (node (ref "U8") (pin "32") (pinfunction "DIO_22_32") (pintype "bidirectional"))
    )
    (net (code "88") (name "unconnected-(U8-DIO_23-Pad36)") (class "Default")
      (node (ref "U8") (pin "36") (pinfunction "DIO_23_36") (pintype "bidirectional"))
    )
    (net (code "89") (name "unconnected-(U8-DIO_24-Pad37)") (class "Default")
      (node (ref "U8") (pin "37") (pinfunction "DIO_24_37") (pintype "bidirectional"))
    )
    (net (code "90") (name "unconnected-(U8-DIO_25-Pad38)") (class "Default")
      (node (ref "U8") (pin "38") (pinfunction "DIO_25_38") (pintype "bidirectional+no_connect"))
    )
    (net (code "91") (name "unconnected-(U8-DIO_26-Pad39)") (class "Default")
      (node (ref "U8") (pin "39") (pinfunction "DIO_26_39") (pintype "bidirectional+no_connect"))
    )
    (net (code "92") (name "unconnected-(U8-DIO_27-Pad40)") (class "Default")
      (node (ref "U8") (pin "40") (pinfunction "DIO_27_40") (pintype "bidirectional+no_connect"))
    )
    (net (code "93") (name "unconnected-(U8-DIO_28-Pad41)") (class "Default")
      (node (ref "U8") (pin "41") (pinfunction "DIO_28_41") (pintype "bidirectional+no_connect"))
    )
    (net (code "94") (name "unconnected-(U8-DIO_29-Pad42)") (class "Default")
      (node (ref "U8") (pin "42") (pinfunction "DIO_29_42") (pintype "bidirectional+no_connect"))
    )
    (net (code "95") (name "unconnected-(U8-DIO_30-Pad43)") (class "Default")
      (node (ref "U8") (pin "43") (pinfunction "DIO_30_43") (pintype "bidirectional+no_connect"))
    )
  )
)
